# 240VAC_dimmer.net
KiCad netlist of a schematic drawn in EAGLE
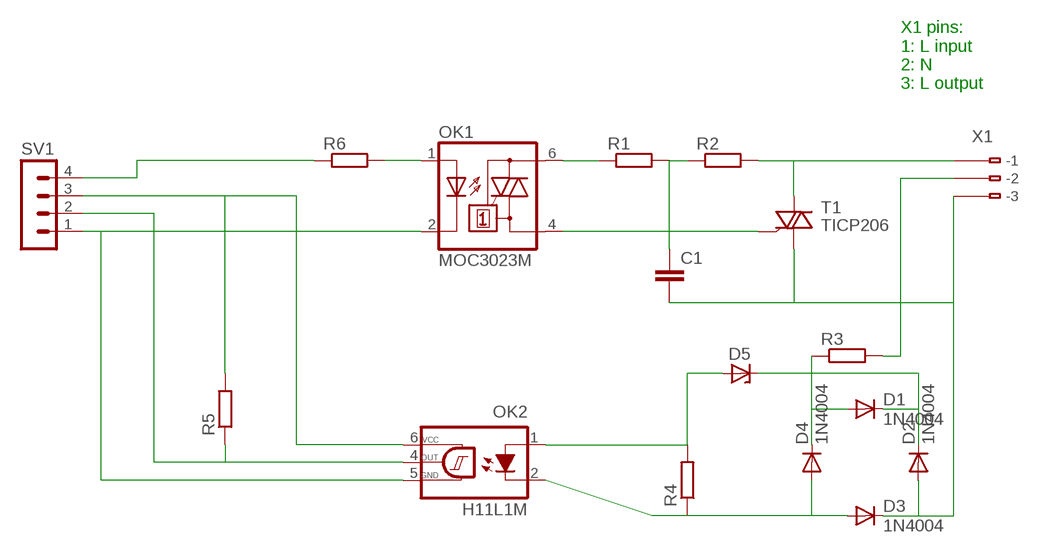
[diagram p0: schematic, sheet 1]

(export (version "E")
  (design (tool "Eeschema 10.0.6"))
  (components
    (comp (ref "C1")
      (value "C-EU050-030X075")
      (footprint "eagle-import:C050-030X075")
      (libsource (lib "eagle-import") (part "C-EU050-030X075"))
    )
    (comp (ref "D1")
      (value "1N4004")
      (footprint "eagle-import:DO41-10")
      (libsource (lib "eagle-import") (part "1N4004"))
    )
    (comp (ref "D2")
      (value "1N4004")
      (footprint "eagle-import:DO41-10")
      (libsource (lib "eagle-import") (part "1N4004"))
    )
    (comp (ref "D3")
      (value "1N4004")
      (footprint "eagle-import:DO41-10")
      (libsource (lib "eagle-import") (part "1N4004"))
    )
    (comp (ref "D4")
      (value "1N4004")
      (footprint "eagle-import:DO41-10")
      (libsource (lib "eagle-import") (part "1N4004"))
    )
    (comp (ref "D5")
      (value "ZENER-DIODEDO41Z10")
      (footprint "eagle-import:DO41Z10")
      (libsource (lib "eagle-import") (part "ZENER-DIODEDO41Z10"))
    )
    (comp (ref "OK1")
      (value "MOC3023M")
      (footprint "eagle-import:DIL06")
      (fields (field (name "MF") "FAIRCHILD SEMICONDUCTOR") (field (name "MPN") "MOC3023-M"))
      (libsource (lib "eagle-import") (part "MOC30M23"))
    )
    (comp (ref "OK2")
      (value "H11L1M")
      (footprint "eagle-import:DIL06")
      (fields (field (name "MF") "FAIRCHILD SEMICONDUCTOR") (field (name "MPN") "H11L1-M"))
      (libsource (lib "eagle-import") (part "H11LM1"))
    )
    (comp (ref "R1")
      (value "R-EU_0411/12")
      (footprint "eagle-import:0411_12")
      (libsource (lib "eagle-import") (part "R-EU_0411/12"))
    )
    (comp (ref "R2")
      (value "R-EU_0411/12")
      (footprint "eagle-import:0411_12")
      (libsource (lib "eagle-import") (part "R-EU_0411/12"))
    )
    (comp (ref "R3")
      (value "R-EU_0207/10")
      (footprint "eagle-import:0207_10")
      (libsource (lib "eagle-import") (part "R-EU_0207/10"))
    )
    (comp (ref "R4")
      (value "R-EU_0204/7")
      (footprint "eagle-import:0204_7")
      (libsource (lib "eagle-import") (part "R-EU_0204/7"))
    )
    (comp (ref "R5")
      (value "R-EU_0204/7")
      (footprint "eagle-import:0204_7")
      (libsource (lib "eagle-import") (part "R-EU_0204/7"))
    )
    (comp (ref "R6")
      (value "R-EU_0204/7")
      (footprint "eagle-import:0204_7")
      (libsource (lib "eagle-import") (part "R-EU_0204/7"))
    )
    (comp (ref "SV1")
      (value "MA04-1")
      (footprint "eagle-import:MA04-1")
      (libsource (lib "eagle-import") (part "MA04-1"))
    )
    (comp (ref "T1")
      (value "TICP206")
      (footprint "eagle-import:TO92-6")
      (libsource (lib "eagle-import") (part "TICP206"))
    )
    (comp (ref "X1")
      (value "233-103")
      (footprint "eagle-import:233-103")
      (libsource (lib "eagle-import") (part "233-103"))
    )
  )
  (nets
    (net (code "1") (name "Net-(C1-Pad1)") (class "Default")
      (node (ref "C1") (pin "1") (pinfunction "1_1") (pintype "passive"))
      (node (ref "R1") (pin "2") (pinfunction "2_2") (pintype "passive"))
      (node (ref "R2") (pin "1") (pinfunction "1_1") (pintype "passive"))
    )
    (net (code "2") (name "Net-(D1-PadA)") (class "Default")
      (node (ref "D1") (pin "A") (pinfunction "A_A") (pintype "passive"))
      (node (ref "D4") (pin "C") (pinfunction "C_C") (pintype "passive"))
      (node (ref "R3") (pin "1") (pinfunction "1_1") (pintype "passive"))
    )
    (net (code "3") (name "Net-(D1-PadC)") (class "Default")
      (node (ref "D1") (pin "C") (pinfunction "C_C") (pintype "passive"))
      (node (ref "D2") (pin "C") (pinfunction "C_C") (pintype "passive"))
      (node (ref "D5") (pin "C") (pinfunction "C_C") (pintype "passive"))
    )
    (net (code "4") (name "Net-(OK1-A)") (class "Default")
      (node (ref "OK1") (pin "1") (pinfunction "A_1") (pintype "passive"))
      (node (ref "R6") (pin "2") (pinfunction "2_2") (pintype "passive"))
    )
    (net (code "5") (name "Net-(OK1-A1)") (class "Default")
      (node (ref "OK1") (pin "4") (pinfunction "A1_4") (pintype "passive"))
      (node (ref "T1") (pin "G") (pinfunction "G_G") (pintype "passive"))
    )
    (net (code "6") (name "Net-(OK1-A2)") (class "Default")
      (node (ref "OK1") (pin "6") (pinfunction "A2_6") (pintype "passive"))
      (node (ref "R1") (pin "1") (pinfunction "1_1") (pintype "passive"))
    )
    (net (code "7") (name "Net-(OK1-C)") (class "Default")
      (node (ref "OK1") (pin "2") (pinfunction "C_2") (pintype "passive"))
      (node (ref "OK2") (pin "5") (pinfunction "GND_5") (pintype "power_in"))
      (node (ref "SV1") (pin "1") (pinfunction "1_1") (pintype "passive"))
    )
    (net (code "8") (name "Net-(OK2-A)") (class "Default")
      (node (ref "D5") (pin "A") (pinfunction "A_A") (pintype "passive"))
      (node (ref "OK2") (pin "1") (pinfunction "A_1") (pintype "passive"))
      (node (ref "R4") (pin "2") (pinfunction "2_2") (pintype "passive"))
    )
    (net (code "9") (name "Net-(OK2-C)") (class "Default")
      (node (ref "D3") (pin "A") (pinfunction "A_A") (pintype "passive"))
      (node (ref "D4") (pin "A") (pinfunction "A_A") (pintype "passive"))
      (node (ref "OK2") (pin "2") (pinfunction "C_2") (pintype "passive"))
      (node (ref "R4") (pin "1") (pinfunction "1_1") (pintype "passive"))
    )
    (net (code "10") (name "Net-(OK2-OUT)") (class "Default")
      (node (ref "OK2") (pin "4") (pinfunction "OUT_4") (pintype "output"))
      (node (ref "R5") (pin "1") (pinfunction "1_1") (pintype "passive"))
      (node (ref "SV1") (pin "2") (pinfunction "2_2") (pintype "passive"))
    )
    (net (code "11") (name "Net-(OK2-VCC)") (class "Default")
      (node (ref "OK2") (pin "6") (pinfunction "VCC_6") (pintype "power_in"))
      (node (ref "R5") (pin "2") (pinfunction "2_2") (pintype "passive"))
      (node (ref "SV1") (pin "3") (pinfunction "3_3") (pintype "passive"))
    )
    (net (code "12") (name "Net-(R6-Pad1)") (class "Default")
      (node (ref "R6") (pin "1") (pinfunction "1_1") (pintype "passive"))
      (node (ref "SV1") (pin "4") (pinfunction "4_4") (pintype "passive"))
    )
    (net (code "13") (name "Net-(X1-B-1)") (class "Default")
      (node (ref "R2") (pin "2") (pinfunction "2_2") (pintype "passive"))
      (node (ref "T1") (pin "A2") (pinfunction "A2_A2") (pintype "passive"))
      (node (ref "X1") (pin "B1") (pinfunction "B-1_B1") (pintype "passive"))
    )
    (net (code "14") (name "Net-(X1-B-2)") (class "Default")
      (node (ref "R3") (pin "2") (pinfunction "2_2") (pintype "passive"))
      (node (ref "X1") (pin "B2") (pinfunction "B-2_B2") (pintype "passive"))
    )
    (net (code "15") (name "Net-(X1-B-3)") (class "Default")
      (node (ref "C1") (pin "2") (pinfunction "2_2") (pintype "passive"))
      (node (ref "D2") (pin "A") (pinfunction "A_A") (pintype "passive"))
      (node (ref "D3") (pin "C") (pinfunction "C_C") (pintype "passive"))
      (node (ref "T1") (pin "A1") (pinfunction "A1_A1") (pintype "passive"))
      (node (ref "X1") (pin "B3") (pinfunction "B-3_B3") (pintype "passive"))
    )
    (net (code "16") (name "unconnected-(X1--1-PadA1)") (class "Default")
      (node (ref "X1") (pin "A1") (pinfunction "-1_A1") (pintype "passive"))
    )
    (net (code "17") (name "unconnected-(X1--2-PadA2)") (class "Default")
      (node (ref "X1") (pin "A2") (pinfunction "-2_A2") (pintype "passive"))
    )
    (net (code "18") (name "unconnected-(X1--3-PadA3)") (class "Default")
      (node (ref "X1") (pin "A3") (pinfunction "-3_A3") (pintype "passive"))
    )
  )
)
